# ovtave_up_SMD_pcbv1.net
KiCad netlist of a schematic drawn in EAGLE
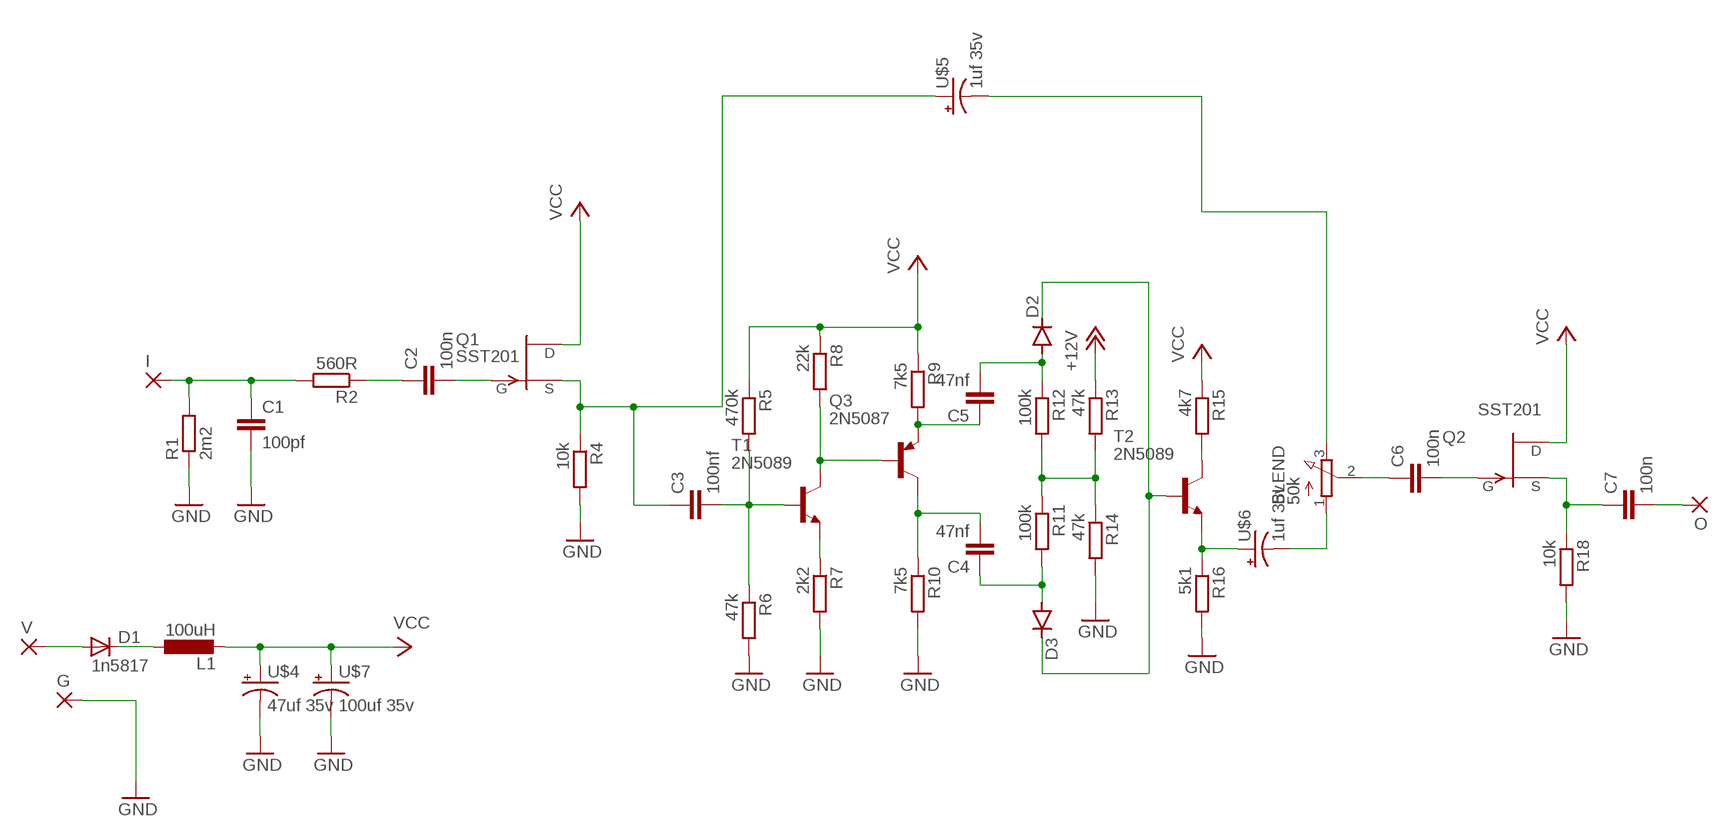
[diagram p0: schematic, sheet 1]

(export (version "E")
  (design (tool "Eeschema 10.0.6"))
  (components
    (comp (ref "BLEND")
      (value "50k")
      (footprint "eagle-import:3RP_1610N")
      (libsource (lib "eagle-import") (part "HEXPOT1"))
    )
    (comp (ref "C1")
      (value "100pf")
      (footprint "eagle-import:C0805K")
      (libsource (lib "eagle-import") (part "C-EUC0805K"))
    )
    (comp (ref "C2")
      (value "100n")
      (footprint "eagle-import:C0805K")
      (libsource (lib "eagle-import") (part "C-EUC0805K"))
    )
    (comp (ref "C3")
      (value "100nf")
      (footprint "eagle-import:C0805K")
      (libsource (lib "eagle-import") (part "C-EUC0805K"))
    )
    (comp (ref "C4")
      (value "47nf")
      (footprint "eagle-import:C0805K")
      (libsource (lib "eagle-import") (part "C-EUC0805K"))
    )
    (comp (ref "C5")
      (value "47nf")
      (footprint "eagle-import:C0805K")
      (libsource (lib "eagle-import") (part "C-EUC0805K"))
    )
    (comp (ref "C6")
      (value "100n")
      (footprint "eagle-import:C0805K")
      (libsource (lib "eagle-import") (part "C-EUC0805K"))
    )
    (comp (ref "C7")
      (value "100n")
      (footprint "eagle-import:C0805K")
      (libsource (lib "eagle-import") (part "C-EUC0805K"))
    )
    (comp (ref "D1")
      (value "1n5817")
      (footprint "eagle-import:DO35-7")
      (libsource (lib "eagle-import") (part "SMALL_DIODEDO35-7"))
    )
    (comp (ref "D2")
      (value "AA112")
      (footprint "eagle-import:DO07")
      (libsource (lib "eagle-import") (part "AA112"))
    )
    (comp (ref "D3")
      (value "AA112")
      (footprint "eagle-import:DO07")
      (libsource (lib "eagle-import") (part "AA112"))
    )
    (comp (ref "G")
      (value "1,6/0,9")
      (footprint "eagle-import:1,6_0,9")
      (libsource (lib "eagle-import") (part "1,6/0,9"))
    )
    (comp (ref "I")
      (value "1,6/0,9")
      (footprint "eagle-import:1,6_0,9")
      (libsource (lib "eagle-import") (part "1,6/0,9"))
    )
    (comp (ref "L1")
      (value "100uH")
      (footprint "eagle-import:L2012C")
      (libsource (lib "eagle-import") (part "L-EUL2012C"))
    )
    (comp (ref "O")
      (value "1,6/0,9")
      (footprint "eagle-import:1,6_0,9")
      (libsource (lib "eagle-import") (part "1,6/0,9"))
    )
    (comp (ref "Q1")
      (value "SST201")
      (footprint "eagle-import:SOT23")
      (libsource (lib "eagle-import") (part "?20SST1"))
    )
    (comp (ref "Q2")
      (value "SST201")
      (footprint "eagle-import:SOT23")
      (libsource (lib "eagle-import") (part "?20SST1"))
    )
    (comp (ref "Q3")
      (value "2N5087")
      (footprint "eagle-import:TO92")
      (libsource (lib "eagle-import") (part "2N5087"))
    )
    (comp (ref "R1")
      (value "2m2")
      (footprint "eagle-import:M0805")
      (libsource (lib "eagle-import") (part "R-EU_M0805"))
    )
    (comp (ref "R2")
      (value "560R")
      (footprint "eagle-import:M0805")
      (libsource (lib "eagle-import") (part "R-EU_M0805"))
    )
    (comp (ref "R4")
      (value "10k")
      (footprint "eagle-import:M0805")
      (libsource (lib "eagle-import") (part "R-EU_M0805"))
    )
    (comp (ref "R5")
      (value "470k")
      (footprint "eagle-import:M0805")
      (libsource (lib "eagle-import") (part "R-EU_M0805"))
    )
    (comp (ref "R6")
      (value "47k")
      (footprint "eagle-import:M0805")
      (libsource (lib "eagle-import") (part "R-EU_M0805"))
    )
    (comp (ref "R7")
      (value "2k2")
      (footprint "eagle-import:M0805")
      (libsource (lib "eagle-import") (part "R-EU_M0805"))
    )
    (comp (ref "R8")
      (value "22k")
      (footprint "eagle-import:M0805")
      (libsource (lib "eagle-import") (part "R-EU_M0805"))
    )
    (comp (ref "R9")
      (value "7k5")
      (footprint "eagle-import:M0805")
      (libsource (lib "eagle-import") (part "R-EU_M0805"))
    )
    (comp (ref "R10")
      (value "7k5")
      (footprint "eagle-import:M0805")
      (libsource (lib "eagle-import") (part "R-EU_M0805"))
    )
    (comp (ref "R11")
      (value "100k")
      (footprint "eagle-import:M0805")
      (libsource (lib "eagle-import") (part "R-EU_M0805"))
    )
    (comp (ref "R12")
      (value "100k")
      (footprint "eagle-import:M0805")
      (libsource (lib "eagle-import") (part "R-EU_M0805"))
    )
    (comp (ref "R13")
      (value "47k")
      (footprint "eagle-import:M0805")
      (libsource (lib "eagle-import") (part "R-EU_M0805"))
    )
    (comp (ref "R14")
      (value "47k")
      (footprint "eagle-import:M0805")
      (libsource (lib "eagle-import") (part "R-EU_M0805"))
    )
    (comp (ref "R15")
      (value "4k7")
      (footprint "eagle-import:M0805")
      (libsource (lib "eagle-import") (part "R-EU_M0805"))
    )
    (comp (ref "R16")
      (value "5k1")
      (footprint "eagle-import:M0805")
      (libsource (lib "eagle-import") (part "R-EU_M0805"))
    )
    (comp (ref "R18")
      (value "10k")
      (footprint "eagle-import:M0805")
      (libsource (lib "eagle-import") (part "R-EU_M0805"))
    )
    (comp (ref "T1")
      (value "2N5089")
      (footprint "eagle-import:TO92")
      (libsource (lib "eagle-import") (part "2N5088"))
    )
    (comp (ref "T2")
      (value "2N5089")
      (footprint "eagle-import:TO92")
      (libsource (lib "eagle-import") (part "2N5088"))
    )
    (comp (ref "U$4")
      (value "47uf 35v")
      (footprint "eagle-import:PAN_B_SMD+THRU")
      (libsource (lib "eagle-import") (part "CAP_SMD+THRUPAN_B"))
    )
    (comp (ref "U$5")
      (value "1uf 35v")
      (footprint "eagle-import:PAN_B_SMD+THRU")
      (libsource (lib "eagle-import") (part "CAP_SMD+THRUPAN_B"))
    )
    (comp (ref "U$6")
      (value "1uf 35v")
      (footprint "eagle-import:PAN_B_SMD+THRU")
      (libsource (lib "eagle-import") (part "CAP_SMD+THRUPAN_B"))
    )
    (comp (ref "U$7")
      (value "100uf 35v")
      (footprint "eagle-import:PAN_C_SMD+THRU")
      (libsource (lib "eagle-import") (part "CAP_SMD+THRUPAN_C"))
    )
    (comp (ref "V")
      (value "1,6/0,9")
      (footprint "eagle-import:1,6_0,9")
      (libsource (lib "eagle-import") (part "1,6/0,9"))
    )
  )
  (nets
    (net (code "1") (name "+12V") (class "Default")
      (node (ref "R13") (pin "1") (pinfunction "1_1") (pintype "passive"))
    )
    (net (code "2") (name "GND") (class "Default")
      (node (ref "C1") (pin "2") (pinfunction "2_2") (pintype "passive"))
      (node (ref "G") (pin "1") (pinfunction "P_1") (pintype "passive"))
      (node (ref "R1") (pin "1") (pinfunction "1_1") (pintype "passive"))
      (node (ref "R10") (pin "2") (pinfunction "2_2") (pintype "passive"))
      (node (ref "R14") (pin "2") (pinfunction "2_2") (pintype "passive"))
      (node (ref "R16") (pin "2") (pinfunction "2_2") (pintype "passive"))
      (node (ref "R18") (pin "2") (pinfunction "2_2") (pintype "passive"))
      (node (ref "R4") (pin "2") (pinfunction "2_2") (pintype "passive"))
      (node (ref "R6") (pin "2") (pinfunction "2_2") (pintype "passive"))
      (node (ref "R7") (pin "2") (pinfunction "2_2") (pintype "passive"))
      (node (ref "U$4") (pin "-") (pinfunction "-_-") (pintype "passive"))
      (node (ref "U$4") (pin "--") (pinfunction "-_--") (pintype "passive"))
      (node (ref "U$7") (pin "-") (pinfunction "-_-") (pintype "passive"))
      (node (ref "U$7") (pin "--") (pinfunction "-_--") (pintype "passive"))
    )
    (net (code "3") (name "Net-(BLEND-A)") (class "Default")
      (node (ref "BLEND") (pin "1") (pinfunction "A_1") (pintype "passive"))
      (node (ref "U$6") (pin "-") (pinfunction "-_-") (pintype "passive"))
      (node (ref "U$6") (pin "--") (pinfunction "-_--") (pintype "passive"))
    )
    (net (code "4") (name "Net-(BLEND-E)") (class "Default")
      (node (ref "BLEND") (pin "3") (pinfunction "E_3") (pintype "passive"))
      (node (ref "U$5") (pin "-") (pinfunction "-_-") (pintype "passive"))
      (node (ref "U$5") (pin "--") (pinfunction "-_--") (pintype "passive"))
    )
    (net (code "5") (name "Net-(BLEND-S)") (class "Default")
      (node (ref "BLEND") (pin "2") (pinfunction "S_2") (pintype "passive"))
      (node (ref "C6") (pin "1") (pinfunction "1_1") (pintype "passive"))
    )
    (net (code "6") (name "Net-(C2-Pad1)") (class "Default")
      (node (ref "C2") (pin "1") (pinfunction "1_1") (pintype "passive"))
      (node (ref "R2") (pin "1") (pinfunction "1_1") (pintype "passive"))
    )
    (net (code "7") (name "Net-(C4-Pad1)") (class "Default")
      (node (ref "C4") (pin "1") (pinfunction "1_1") (pintype "passive"))
      (node (ref "D3") (pin "A") (pinfunction "A_A") (pintype "passive"))
      (node (ref "R11") (pin "2") (pinfunction "2_2") (pintype "passive"))
    )
    (net (code "8") (name "Net-(C5-Pad2)") (class "Default")
      (node (ref "C5") (pin "2") (pinfunction "2_2") (pintype "passive"))
      (node (ref "D2") (pin "A") (pinfunction "A_A") (pintype "passive"))
      (node (ref "R12") (pin "1") (pinfunction "1_1") (pintype "passive"))
    )
    (net (code "9") (name "Net-(D1-PadC)") (class "Default")
      (node (ref "D1") (pin "C") (pinfunction "C_C") (pintype "passive"))
      (node (ref "L1") (pin "1") (pinfunction "1_1") (pintype "passive"))
    )
    (net (code "10") (name "Net-(I-P)") (class "Default")
      (node (ref "C1") (pin "1") (pinfunction "1_1") (pintype "passive"))
      (node (ref "I") (pin "1") (pinfunction "P_1") (pintype "passive"))
      (node (ref "R1") (pin "2") (pinfunction "2_2") (pintype "passive"))
      (node (ref "R2") (pin "2") (pinfunction "2_2") (pintype "passive"))
    )
    (net (code "11") (name "Net-(O-P)") (class "Default")
      (node (ref "C7") (pin "2") (pinfunction "2_2") (pintype "passive"))
      (node (ref "O") (pin "1") (pinfunction "P_1") (pintype "passive"))
    )
    (net (code "12") (name "Net-(Q1-G)") (class "Default")
      (node (ref "C2") (pin "2") (pinfunction "2_2") (pintype "passive"))
      (node (ref "Q1") (pin "3") (pinfunction "G_3") (pintype "passive"))
    )
    (net (code "13") (name "Net-(Q1-S)") (class "Default")
      (node (ref "C3") (pin "1") (pinfunction "1_1") (pintype "passive"))
      (node (ref "Q1") (pin "2") (pinfunction "S_2") (pintype "passive"))
      (node (ref "R4") (pin "1") (pinfunction "1_1") (pintype "passive"))
      (node (ref "U$5") (pin "+") (pinfunction "+_+") (pintype "passive"))
      (node (ref "U$5") (pin "++") (pinfunction "+_++") (pintype "passive"))
    )
    (net (code "14") (name "Net-(Q2-G)") (class "Default")
      (node (ref "C6") (pin "2") (pinfunction "2_2") (pintype "passive"))
      (node (ref "Q2") (pin "3") (pinfunction "G_3") (pintype "passive"))
    )
    (net (code "15") (name "Net-(Q2-S)") (class "Default")
      (node (ref "C7") (pin "1") (pinfunction "1_1") (pintype "passive"))
      (node (ref "Q2") (pin "2") (pinfunction "S_2") (pintype "passive"))
      (node (ref "R18") (pin "1") (pinfunction "1_1") (pintype "passive"))
    )
    (net (code "16") (name "Net-(Q3-B)") (class "Default")
      (node (ref "Q3") (pin "2") (pinfunction "B_2") (pintype "passive"))
      (node (ref "R8") (pin "2") (pinfunction "2_2") (pintype "passive"))
      (node (ref "T1") (pin "1") (pinfunction "C_1") (pintype "passive"))
    )
    (net (code "17") (name "Net-(Q3-C)") (class "Default")
      (node (ref "C4") (pin "2") (pinfunction "2_2") (pintype "passive"))
      (node (ref "Q3") (pin "1") (pinfunction "C_1") (pintype "passive"))
      (node (ref "R10") (pin "1") (pinfunction "1_1") (pintype "passive"))
    )
    (net (code "18") (name "Net-(Q3-E)") (class "Default")
      (node (ref "C5") (pin "1") (pinfunction "1_1") (pintype "passive"))
      (node (ref "Q3") (pin "3") (pinfunction "E_3") (pintype "passive"))
      (node (ref "R9") (pin "2") (pinfunction "2_2") (pintype "passive"))
    )
    (net (code "19") (name "Net-(R11-Pad1)") (class "Default")
      (node (ref "R11") (pin "1") (pinfunction "1_1") (pintype "passive"))
      (node (ref "R12") (pin "2") (pinfunction "2_2") (pintype "passive"))
      (node (ref "R13") (pin "2") (pinfunction "2_2") (pintype "passive"))
      (node (ref "R14") (pin "1") (pinfunction "1_1") (pintype "passive"))
    )
    (net (code "20") (name "Net-(T1-B)") (class "Default")
      (node (ref "C3") (pin "2") (pinfunction "2_2") (pintype "passive"))
      (node (ref "R5") (pin "2") (pinfunction "2_2") (pintype "passive"))
      (node (ref "R6") (pin "1") (pinfunction "1_1") (pintype "passive"))
      (node (ref "T1") (pin "2") (pinfunction "B_2") (pintype "passive"))
    )
    (net (code "21") (name "Net-(T1-E)") (class "Default")
      (node (ref "R7") (pin "1") (pinfunction "1_1") (pintype "passive"))
      (node (ref "T1") (pin "3") (pinfunction "E_3") (pintype "passive"))
    )
    (net (code "22") (name "Net-(T2-B)") (class "Default")
      (node (ref "D2") (pin "C") (pinfunction "C_C") (pintype "passive"))
      (node (ref "D3") (pin "C") (pinfunction "C_C") (pintype "passive"))
      (node (ref "T2") (pin "2") (pinfunction "B_2") (pintype "passive"))
    )
    (net (code "23") (name "Net-(T2-C)") (class "Default")
      (node (ref "R15") (pin "2") (pinfunction "2_2") (pintype "passive"))
      (node (ref "T2") (pin "1") (pinfunction "C_1") (pintype "passive"))
    )
    (net (code "24") (name "Net-(T2-E)") (class "Default")
      (node (ref "R16") (pin "1") (pinfunction "1_1") (pintype "passive"))
      (node (ref "T2") (pin "3") (pinfunction "E_3") (pintype "passive"))
      (node (ref "U$6") (pin "+") (pinfunction "+_+") (pintype "passive"))
      (node (ref "U$6") (pin "++") (pinfunction "+_++") (pintype "passive"))
    )
    (net (code "25") (name "Net-(V-P)") (class "Default")
      (node (ref "D1") (pin "A") (pinfunction "A_A") (pintype "passive"))
      (node (ref "V") (pin "1") (pinfunction "P_1") (pintype "passive"))
    )
    (net (code "26") (name "VCC") (class "Default")
      (node (ref "L1") (pin "2") (pinfunction "2_2") (pintype "passive"))
      (node (ref "Q1") (pin "1") (pinfunction "D_1") (pintype "passive"))
      (node (ref "Q2") (pin "1") (pinfunction "D_1") (pintype "passive"))
      (node (ref "R15") (pin "1") (pinfunction "1_1") (pintype "passive"))
      (node (ref "R5") (pin "1") (pinfunction "1_1") (pintype "passive"))
      (node (ref "R8") (pin "1") (pinfunction "1_1") (pintype "passive"))
      (node (ref "R9") (pin "1") (pinfunction "1_1") (pintype "passive"))
      (node (ref "U$4") (pin "+") (pinfunction "+_+") (pintype "passive"))
      (node (ref "U$4") (pin "++") (pinfunction "+_++") (pintype "passive"))
      (node (ref "U$7") (pin "+") (pinfunction "+_+") (pintype "passive"))
      (node (ref "U$7") (pin "++") (pinfunction "+_++") (pintype "passive"))
    )
  )
)
